# Main.net
KiCad netlist of a schematic drawn in EAGLE
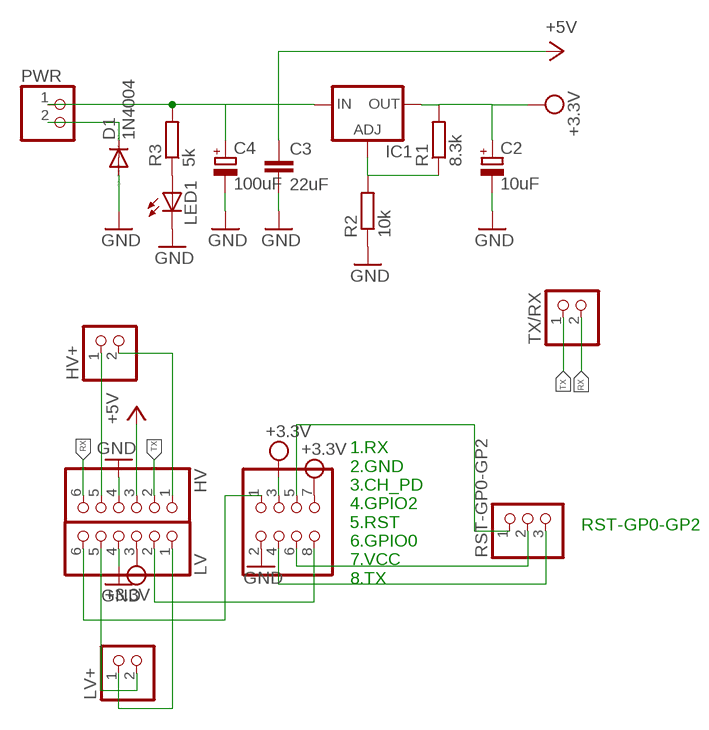
[diagram p0: schematic, sheet 1]

(export (version "E")
  (design (tool "Eeschema 10.0.6"))
  (components
    (comp (ref "C2")
      (value "10uF")
      (footprint "eagle-import:E2-5")
      (libsource (lib "eagle-import") (part "CPOL-EUE2-5"))
    )
    (comp (ref "C3")
      (value "22uF")
      (footprint "eagle-import:C025-024X044")
      (libsource (lib "eagle-import") (part "C-EU025-024X044"))
    )
    (comp (ref "C4")
      (value "100uF")
      (footprint "eagle-import:E2,5-7")
      (libsource (lib "eagle-import") (part "CPOL-EUE2.5-7"))
    )
    (comp (ref "D1")
      (value "1N4004")
      (footprint "eagle-import:DO41-10")
      (libsource (lib "eagle-import") (part "1N4004"))
    )
    (comp (ref "HV")
      (value "PINHD-1X6")
      (footprint "eagle-import:1X06")
      (libsource (lib "eagle-import") (part "PINHD-1X6"))
    )
    (comp (ref "HV+")
      (value "PINHD-1X2")
      (footprint "eagle-import:1X02")
      (libsource (lib "eagle-import") (part "PINHD-1X2"))
    )
    (comp (ref "IC1")
      (value "LM317TS")
      (footprint "eagle-import:317TS")
      (libsource (lib "eagle-import") (part "LM317TS"))
    )
    (comp (ref "LED1")
      (value "LED5MM")
      (footprint "eagle-import:LED5MM")
      (libsource (lib "eagle-import") (part "LED5MM"))
    )
    (comp (ref "LV")
      (value "PINHD-1X6")
      (footprint "eagle-import:1X06")
      (libsource (lib "eagle-import") (part "PINHD-1X6"))
    )
    (comp (ref "LV+")
      (value "PINHD-1X2")
      (footprint "eagle-import:1X02")
      (libsource (lib "eagle-import") (part "PINHD-1X2"))
    )
    (comp (ref "PWR")
      (value "PINHD-1X2")
      (footprint "eagle-import:1X02")
      (libsource (lib "eagle-import") (part "PINHD-1X2"))
    )
    (comp (ref "R1")
      (value "8.3k")
      (footprint "eagle-import:0207_7")
      (libsource (lib "eagle-import") (part "R-EU_0207/7"))
    )
    (comp (ref "R2")
      (value "10k")
      (footprint "eagle-import:0207_7")
      (libsource (lib "eagle-import") (part "R-EU_0207/7"))
    )
    (comp (ref "R3")
      (value "5k")
      (footprint "eagle-import:0207_7")
      (libsource (lib "eagle-import") (part "R-EU_0207/7"))
    )
    (comp (ref "RST-GP0-GP2")
      (value "PINHD-1X3")
      (footprint "eagle-import:1X03")
      (libsource (lib "eagle-import") (part "PINHD-1X3"))
    )
    (comp (ref "SOCLU_ESP")
      (value "PINHD-2X4")
      (footprint "eagle-import:2X04")
      (libsource (lib "eagle-import") (part "PINHD-2X4"))
    )
    (comp (ref "TX/RX")
      (value "PINHD-1X2")
      (footprint "eagle-import:1X02")
      (libsource (lib "eagle-import") (part "PINHD-1X2"))
    )
  )
  (nets
    (net (code "1") (name "+3.3V") (class "Default")
      (node (ref "C2") (pin "+") (pinfunction "+_+") (pintype "passive"))
      (node (ref "IC1") (pin "2") (pinfunction "OUT_2") (pintype "passive"))
      (node (ref "LV") (pin "3") (pinfunction "3_3") (pintype "passive"))
      (node (ref "R1") (pin "2") (pinfunction "2_2") (pintype "passive"))
      (node (ref "SOCLU_ESP") (pin "3") (pinfunction "3_3") (pintype "passive"))
      (node (ref "SOCLU_ESP") (pin "7") (pinfunction "7_7") (pintype "passive"))
    )
    (net (code "2") (name "+5V") (class "Default")
      (node (ref "C3") (pin "1") (pinfunction "1_1") (pintype "passive"))
      (node (ref "C4") (pin "+") (pinfunction "+_+") (pintype "passive"))
      (node (ref "HV") (pin "3") (pinfunction "3_3") (pintype "passive"))
      (node (ref "IC1") (pin "3") (pinfunction "IN_3") (pintype "input"))
      (node (ref "PWR") (pin "1") (pinfunction "1_1") (pintype "passive"))
      (node (ref "R3") (pin "2") (pinfunction "2_2") (pintype "passive"))
    )
    (net (code "3") (name "GND") (class "Default")
      (node (ref "C2") (pin "-") (pinfunction "-_-") (pintype "passive"))
      (node (ref "C3") (pin "2") (pinfunction "2_2") (pintype "passive"))
      (node (ref "C4") (pin "-") (pinfunction "-_-") (pintype "passive"))
      (node (ref "D1") (pin "A") (pinfunction "A_A") (pintype "passive"))
      (node (ref "HV") (pin "4") (pinfunction "4_4") (pintype "passive"))
      (node (ref "LED1") (pin "K") (pinfunction "C_K") (pintype "passive"))
      (node (ref "LV") (pin "4") (pinfunction "4_4") (pintype "passive"))
      (node (ref "R2") (pin "1") (pinfunction "1_1") (pintype "passive"))
      (node (ref "SOCLU_ESP") (pin "2") (pinfunction "2_2") (pintype "passive"))
    )
    (net (code "4") (name "Net-(D1-PadC)") (class "Default")
      (node (ref "D1") (pin "C") (pinfunction "C_C") (pintype "passive"))
      (node (ref "PWR") (pin "2") (pinfunction "2_2") (pintype "passive"))
    )
    (net (code "5") (name "Net-(HV+-Pad1)") (class "Default")
      (node (ref "HV") (pin "5") (pinfunction "5_5") (pintype "passive"))
      (node (ref "HV+") (pin "1") (pinfunction "1_1") (pintype "passive"))
    )
    (net (code "6") (name "Net-(HV+-Pad2)") (class "Default")
      (node (ref "HV") (pin "1") (pinfunction "1_1") (pintype "passive"))
      (node (ref "HV+") (pin "2") (pinfunction "2_2") (pintype "passive"))
    )
    (net (code "7") (name "Net-(IC1-ADJ)") (class "Default")
      (node (ref "IC1") (pin "1") (pinfunction "ADJ_1") (pintype "input"))
      (node (ref "R1") (pin "1") (pinfunction "1_1") (pintype "passive"))
      (node (ref "R2") (pin "2") (pinfunction "2_2") (pintype "passive"))
    )
    (net (code "8") (name "Net-(LED1-PadA)") (class "Default")
      (node (ref "LED1") (pin "A") (pinfunction "A_A") (pintype "passive"))
      (node (ref "R3") (pin "1") (pinfunction "1_1") (pintype "passive"))
    )
    (net (code "9") (name "Net-(LV+-Pad1)") (class "Default")
      (node (ref "LV") (pin "1") (pinfunction "1_1") (pintype "passive"))
      (node (ref "LV+") (pin "1") (pinfunction "1_1") (pintype "passive"))
    )
    (net (code "10") (name "Net-(LV+-Pad2)") (class "Default")
      (node (ref "LV") (pin "5") (pinfunction "5_5") (pintype "passive"))
      (node (ref "LV+") (pin "2") (pinfunction "2_2") (pintype "passive"))
    )
    (net (code "11") (name "Net-(LV-Pad2)") (class "Default")
      (node (ref "LV") (pin "2") (pinfunction "2_2") (pintype "passive"))
      (node (ref "SOCLU_ESP") (pin "8") (pinfunction "8_8") (pintype "passive"))
    )
    (net (code "12") (name "Net-(LV-Pad6)") (class "Default")
      (node (ref "LV") (pin "6") (pinfunction "6_6") (pintype "passive"))
      (node (ref "SOCLU_ESP") (pin "1") (pinfunction "1_1") (pintype "passive"))
    )
    (net (code "13") (name "Net-(RST-GP0-GP2-Pad1)") (class "Default")
      (node (ref "RST-GP0-GP2") (pin "1") (pinfunction "1_1") (pintype "passive"))
      (node (ref "SOCLU_ESP") (pin "5") (pinfunction "5_5") (pintype "passive"))
    )
    (net (code "14") (name "Net-(RST-GP0-GP2-Pad2)") (class "Default")
      (node (ref "RST-GP0-GP2") (pin "2") (pinfunction "2_2") (pintype "passive"))
      (node (ref "SOCLU_ESP") (pin "6") (pinfunction "6_6") (pintype "passive"))
    )
    (net (code "15") (name "Net-(RST-GP0-GP2-Pad3)") (class "Default")
      (node (ref "RST-GP0-GP2") (pin "3") (pinfunction "3_3") (pintype "passive"))
      (node (ref "SOCLU_ESP") (pin "4") (pinfunction "4_4") (pintype "passive"))
    )
    (net (code "16") (name "RX") (class "Default")
      (node (ref "HV") (pin "6") (pinfunction "6_6") (pintype "passive"))
      (node (ref "TX/RX") (pin "2") (pinfunction "2_2") (pintype "passive"))
    )
    (net (code "17") (name "TX") (class "Default")
      (node (ref "HV") (pin "2") (pinfunction "2_2") (pintype "passive"))
      (node (ref "TX/RX") (pin "1") (pinfunction "1_1") (pintype "passive"))
    )
  )
)
